# 3_3-5V_Signal.net
KiCad netlist of a schematic drawn in EAGLE
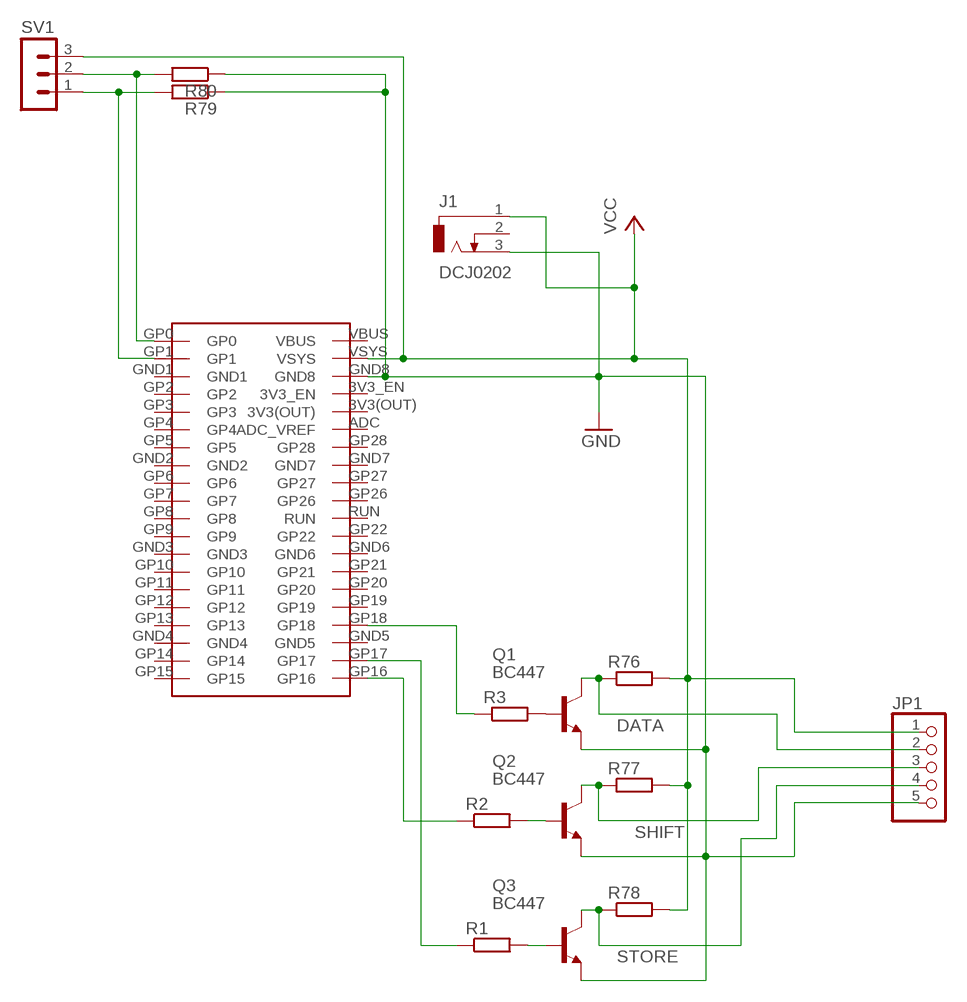
[diagram p0: schematic, sheet 1]

(export (version "E")
  (design (tool "Eeschema 10.0.6"))
  (components
    (comp (ref "J1")
      (value "DCJ0202")
      (footprint "eagle-import:DCJ0202")
      (libsource (lib "eagle-import") (part "DCJ0202"))
    )
    (comp (ref "JP1")
      (value "PINHD-1X5")
      (footprint "eagle-import:1X05")
      (libsource (lib "eagle-import") (part "PINHD-1X5"))
    )
    (comp (ref "Q1")
      (value "BC447")
      (footprint "eagle-import:TO92-EBC")
      (libsource (lib "eagle-import") (part "BC447"))
    )
    (comp (ref "Q2")
      (value "BC447")
      (footprint "eagle-import:TO92-EBC")
      (libsource (lib "eagle-import") (part "BC447"))
    )
    (comp (ref "Q3")
      (value "BC447")
      (footprint "eagle-import:TO92-EBC")
      (libsource (lib "eagle-import") (part "BC447"))
    )
    (comp (ref "R1")
      (value "R-EU_0207/10")
      (footprint "eagle-import:0207_10")
      (libsource (lib "eagle-import") (part "R-EU_0207/10"))
    )
    (comp (ref "R2")
      (value "R-EU_0207/10")
      (footprint "eagle-import:0207_10")
      (libsource (lib "eagle-import") (part "R-EU_0207/10"))
    )
    (comp (ref "R3")
      (value "R-EU_0207/10")
      (footprint "eagle-import:0207_10")
      (libsource (lib "eagle-import") (part "R-EU_0207/10"))
    )
    (comp (ref "R76")
      (value "R-EU_0207/10")
      (footprint "eagle-import:0207_10")
      (libsource (lib "eagle-import") (part "R-EU_0207/10"))
    )
    (comp (ref "R77")
      (value "R-EU_0207/10")
      (footprint "eagle-import:0207_10")
      (libsource (lib "eagle-import") (part "R-EU_0207/10"))
    )
    (comp (ref "R78")
      (value "R-EU_0207/10")
      (footprint "eagle-import:0207_10")
      (libsource (lib "eagle-import") (part "R-EU_0207/10"))
    )
    (comp (ref "R79")
      (value "R-EU_0207/10")
      (footprint "eagle-import:0207_10")
      (libsource (lib "eagle-import") (part "R-EU_0207/10"))
    )
    (comp (ref "R80")
      (value "R-EU_0207/10")
      (footprint "eagle-import:0207_10")
      (libsource (lib "eagle-import") (part "R-EU_0207/10"))
    )
    (comp (ref "SV1")
      (value "MA03-1")
      (footprint "eagle-import:MA03-1")
      (libsource (lib "eagle-import") (part "MA03-1"))
    )
    (comp (ref "U$2")
      (value "PI_PICO")
      (footprint "eagle-import:PI_PICO")
      (libsource (lib "eagle-import") (part "PI_PICO"))
    )
  )
  (nets
    (net (code "1") (name "/DATA") (class "Default")
      (node (ref "JP1") (pin "2") (pinfunction "2_2") (pintype "passive"))
      (node (ref "Q1") (pin "C") (pinfunction "C_C") (pintype "passive"))
      (node (ref "R76") (pin "1") (pinfunction "1_1") (pintype "passive"))
    )
    (net (code "2") (name "/SHIFT") (class "Default")
      (node (ref "JP1") (pin "3") (pinfunction "3_3") (pintype "passive"))
      (node (ref "Q2") (pin "C") (pinfunction "C_C") (pintype "passive"))
      (node (ref "R77") (pin "1") (pinfunction "1_1") (pintype "passive"))
    )
    (net (code "3") (name "/STORE") (class "Default")
      (node (ref "JP1") (pin "4") (pinfunction "4_4") (pintype "passive"))
      (node (ref "Q3") (pin "C") (pinfunction "C_C") (pintype "passive"))
      (node (ref "R78") (pin "1") (pinfunction "1_1") (pintype "passive"))
    )
    (net (code "4") (name "GND") (class "Default")
      (node (ref "J1") (pin "3") (pinfunction "3_3") (pintype "passive"))
      (node (ref "JP1") (pin "5") (pinfunction "5_5") (pintype "passive"))
      (node (ref "Q1") (pin "E") (pinfunction "E_E") (pintype "passive"))
      (node (ref "Q2") (pin "E") (pinfunction "E_E") (pintype "passive"))
      (node (ref "Q3") (pin "E") (pinfunction "E_E") (pintype "passive"))
      (node (ref "R79") (pin "1") (pinfunction "1_1") (pintype "passive"))
      (node (ref "R80") (pin "1") (pinfunction "1_1") (pintype "passive"))
      (node (ref "U$2") (pin "GND8") (pinfunction "GND8_GND8") (pintype "bidirectional"))
    )
    (net (code "5") (name "Net-(Q1-PadB)") (class "Default")
      (node (ref "Q1") (pin "B") (pinfunction "B_B") (pintype "passive"))
      (node (ref "R3") (pin "2") (pinfunction "2_2") (pintype "passive"))
    )
    (net (code "6") (name "Net-(Q2-PadB)") (class "Default")
      (node (ref "Q2") (pin "B") (pinfunction "B_B") (pintype "passive"))
      (node (ref "R2") (pin "2") (pinfunction "2_2") (pintype "passive"))
    )
    (net (code "7") (name "Net-(Q3-PadB)") (class "Default")
      (node (ref "Q3") (pin "B") (pinfunction "B_B") (pintype "passive"))
      (node (ref "R1") (pin "2") (pinfunction "2_2") (pintype "passive"))
    )
    (net (code "8") (name "Net-(R1-Pad1)") (class "Default")
      (node (ref "R1") (pin "1") (pinfunction "1_1") (pintype "passive"))
      (node (ref "U$2") (pin "GP17") (pinfunction "GP17_GP17") (pintype "bidirectional"))
    )
    (net (code "9") (name "Net-(R2-Pad1)") (class "Default")
      (node (ref "R2") (pin "1") (pinfunction "1_1") (pintype "passive"))
      (node (ref "U$2") (pin "GP16") (pinfunction "GP16_GP16") (pintype "bidirectional"))
    )
    (net (code "10") (name "Net-(R3-Pad1)") (class "Default")
      (node (ref "R3") (pin "1") (pinfunction "1_1") (pintype "passive"))
      (node (ref "U$2") (pin "GP18") (pinfunction "GP18_GP18") (pintype "bidirectional"))
    )
    (net (code "11") (name "Net-(R79-Pad2)") (class "Default")
      (node (ref "R79") (pin "2") (pinfunction "2_2") (pintype "passive"))
      (node (ref "SV1") (pin "1") (pinfunction "1_1") (pintype "passive"))
      (node (ref "U$2") (pin "GP1") (pinfunction "GP1_GP1") (pintype "bidirectional"))
    )
    (net (code "12") (name "Net-(R80-Pad2)") (class "Default")
      (node (ref "R80") (pin "2") (pinfunction "2_2") (pintype "passive"))
      (node (ref "SV1") (pin "2") (pinfunction "2_2") (pintype "passive"))
      (node (ref "U$2") (pin "GP0") (pinfunction "GP0_GP0") (pintype "bidirectional"))
    )
    (net (code "13") (name "VCC") (class "Default")
      (node (ref "J1") (pin "1") (pinfunction "1_1") (pintype "passive"))
      (node (ref "JP1") (pin "1") (pinfunction "1_1") (pintype "passive"))
      (node (ref "R76") (pin "2") (pinfunction "2_2") (pintype "passive"))
      (node (ref "R77") (pin "2") (pinfunction "2_2") (pintype "passive"))
      (node (ref "R78") (pin "2") (pinfunction "2_2") (pintype "passive"))
      (node (ref "SV1") (pin "3") (pinfunction "3_3") (pintype "passive"))
      (node (ref "U$2") (pin "VSYS") (pinfunction "VSYS_VSYS") (pintype "bidirectional"))
    )
    (net (code "14") (name "unconnected-(J1-Pad2)") (class "Default")
      (node (ref "J1") (pin "2") (pinfunction "2_2") (pintype "passive"))
    )
    (net (code "15") (name "unconnected-(U$2-ADC_VREF-PadADC)") (class "Default")
      (node (ref "U$2") (pin "ADC") (pinfunction "ADC_VREF_ADC") (pintype "bidirectional"))
    )
    (net (code "16") (name "unconnected-(U$2-Pad3V3(OUT))") (class "Default")
      (node (ref "U$2") (pin "3V3(OUT)") (pinfunction "3V3(OUT)_3V3(OUT)") (pintype "bidirectional"))
    )
    (net (code "17") (name "unconnected-(U$2-Pad3V3_EN)") (class "Default")
      (node (ref "U$2") (pin "3V3_EN") (pinfunction "3V3_EN_3V3_EN") (pintype "bidirectional"))
    )
    (net (code "18") (name "unconnected-(U$2-PadGND1)") (class "Default")
      (node (ref "U$2") (pin "GND1") (pinfunction "GND1_GND1") (pintype "bidirectional"))
    )
    (net (code "19") (name "unconnected-(U$2-PadGND2)") (class "Default")
      (node (ref "U$2") (pin "GND2") (pinfunction "GND2_GND2") (pintype "bidirectional"))
    )
    (net (code "20") (name "unconnected-(U$2-PadGND3)") (class "Default")
      (node (ref "U$2") (pin "GND3") (pinfunction "GND3_GND3") (pintype "bidirectional"))
    )
    (net (code "21") (name "unconnected-(U$2-PadGND4)") (class "Default")
      (node (ref "U$2") (pin "GND4") (pinfunction "GND4_GND4") (pintype "bidirectional"))
    )
    (net (code "22") (name "unconnected-(U$2-PadGND5)") (class "Default")
      (node (ref "U$2") (pin "GND5") (pinfunction "GND5_GND5") (pintype "bidirectional"))
    )
    (net (code "23") (name "unconnected-(U$2-PadGND6)") (class "Default")
      (node (ref "U$2") (pin "GND6") (pinfunction "GND6_GND6") (pintype "bidirectional"))
    )
    (net (code "24") (name "unconnected-(U$2-PadGND7)") (class "Default")
      (node (ref "U$2") (pin "GND7") (pinfunction "GND7_GND7") (pintype "bidirectional"))
    )
    (net (code "25") (name "unconnected-(U$2-PadGP2)") (class "Default")
      (node (ref "U$2") (pin "GP2") (pinfunction "GP2_GP2") (pintype "bidirectional"))
    )
    (net (code "26") (name "unconnected-(U$2-PadGP3)") (class "Default")
      (node (ref "U$2") (pin "GP3") (pinfunction "GP3_GP3") (pintype "bidirectional"))
    )
    (net (code "27") (name "unconnected-(U$2-PadGP4)") (class "Default")
      (node (ref "U$2") (pin "GP4") (pinfunction "GP4_GP4") (pintype "bidirectional"))
    )
    (net (code "28") (name "unconnected-(U$2-PadGP5)") (class "Default")
      (node (ref "U$2") (pin "GP5") (pinfunction "GP5_GP5") (pintype "bidirectional"))
    )
    (net (code "29") (name "unconnected-(U$2-PadGP6)") (class "Default")
      (node (ref "U$2") (pin "GP6") (pinfunction "GP6_GP6") (pintype "bidirectional"))
    )
    (net (code "30") (name "unconnected-(U$2-PadGP7)") (class "Default")
      (node (ref "U$2") (pin "GP7") (pinfunction "GP7_GP7") (pintype "bidirectional"))
    )
    (net (code "31") (name "unconnected-(U$2-PadGP8)") (class "Default")
      (node (ref "U$2") (pin "GP8") (pinfunction "GP8_GP8") (pintype "bidirectional"))
    )
    (net (code "32") (name "unconnected-(U$2-PadGP9)") (class "Default")
      (node (ref "U$2") (pin "GP9") (pinfunction "GP9_GP9") (pintype "bidirectional"))
    )
    (net (code "33") (name "unconnected-(U$2-PadGP10)") (class "Default")
      (node (ref "U$2") (pin "GP10") (pinfunction "GP10_GP10") (pintype "bidirectional"))
    )
    (net (code "34") (name "unconnected-(U$2-PadGP11)") (class "Default")
      (node (ref "U$2") (pin "GP11") (pinfunction "GP11_GP11") (pintype "bidirectional"))
    )
    (net (code "35") (name "unconnected-(U$2-PadGP12)") (class "Default")
      (node (ref "U$2") (pin "GP12") (pinfunction "GP12_GP12") (pintype "bidirectional"))
    )
    (net (code "36") (name "unconnected-(U$2-PadGP13)") (class "Default")
      (node (ref "U$2") (pin "GP13") (pinfunction "GP13_GP13") (pintype "bidirectional"))
    )
    (net (code "37") (name "unconnected-(U$2-PadGP14)") (class "Default")
      (node (ref "U$2") (pin "GP14") (pinfunction "GP14_GP14") (pintype "bidirectional"))
    )
    (net (code "38") (name "unconnected-(U$2-PadGP15)") (class "Default")
      (node (ref "U$2") (pin "GP15") (pinfunction "GP15_GP15") (pintype "bidirectional"))
    )
    (net (code "39") (name "unconnected-(U$2-PadGP19)") (class "Default")
      (node (ref "U$2") (pin "GP19") (pinfunction "GP19_GP19") (pintype "bidirectional"))
    )
    (net (code "40") (name "unconnected-(U$2-PadGP20)") (class "Default")
      (node (ref "U$2") (pin "GP20") (pinfunction "GP20_GP20") (pintype "bidirectional"))
    )
    (net (code "41") (name "unconnected-(U$2-PadGP21)") (class "Default")
      (node (ref "U$2") (pin "GP21") (pinfunction "GP21_GP21") (pintype "bidirectional"))
    )
    (net (code "42") (name "unconnected-(U$2-PadGP22)") (class "Default")
      (node (ref "U$2") (pin "GP22") (pinfunction "GP22_GP22") (pintype "bidirectional"))
    )
    (net (code "43") (name "unconnected-(U$2-PadGP26)") (class "Default")
      (node (ref "U$2") (pin "GP26") (pinfunction "GP26_GP26") (pintype "bidirectional"))
    )
    (net (code "44") (name "unconnected-(U$2-PadGP27)") (class "Default")
      (node (ref "U$2") (pin "GP27") (pinfunction "GP27_GP27") (pintype "bidirectional"))
    )
    (net (code "45") (name "unconnected-(U$2-PadGP28)") (class "Default")
      (node (ref "U$2") (pin "GP28") (pinfunction "GP28_GP28") (pintype "bidirectional"))
    )
    (net (code "46") (name "unconnected-(U$2-PadRUN)") (class "Default")
      (node (ref "U$2") (pin "RUN") (pinfunction "RUN_RUN") (pintype "bidirectional"))
    )
    (net (code "47") (name "unconnected-(U$2-PadVBUS)") (class "Default")
      (node (ref "U$2") (pin "VBUS") (pinfunction "VBUS_VBUS") (pintype "bidirectional"))
    )
  )
)
